# main.net
KiCad netlist of a schematic drawn in Altium Designer
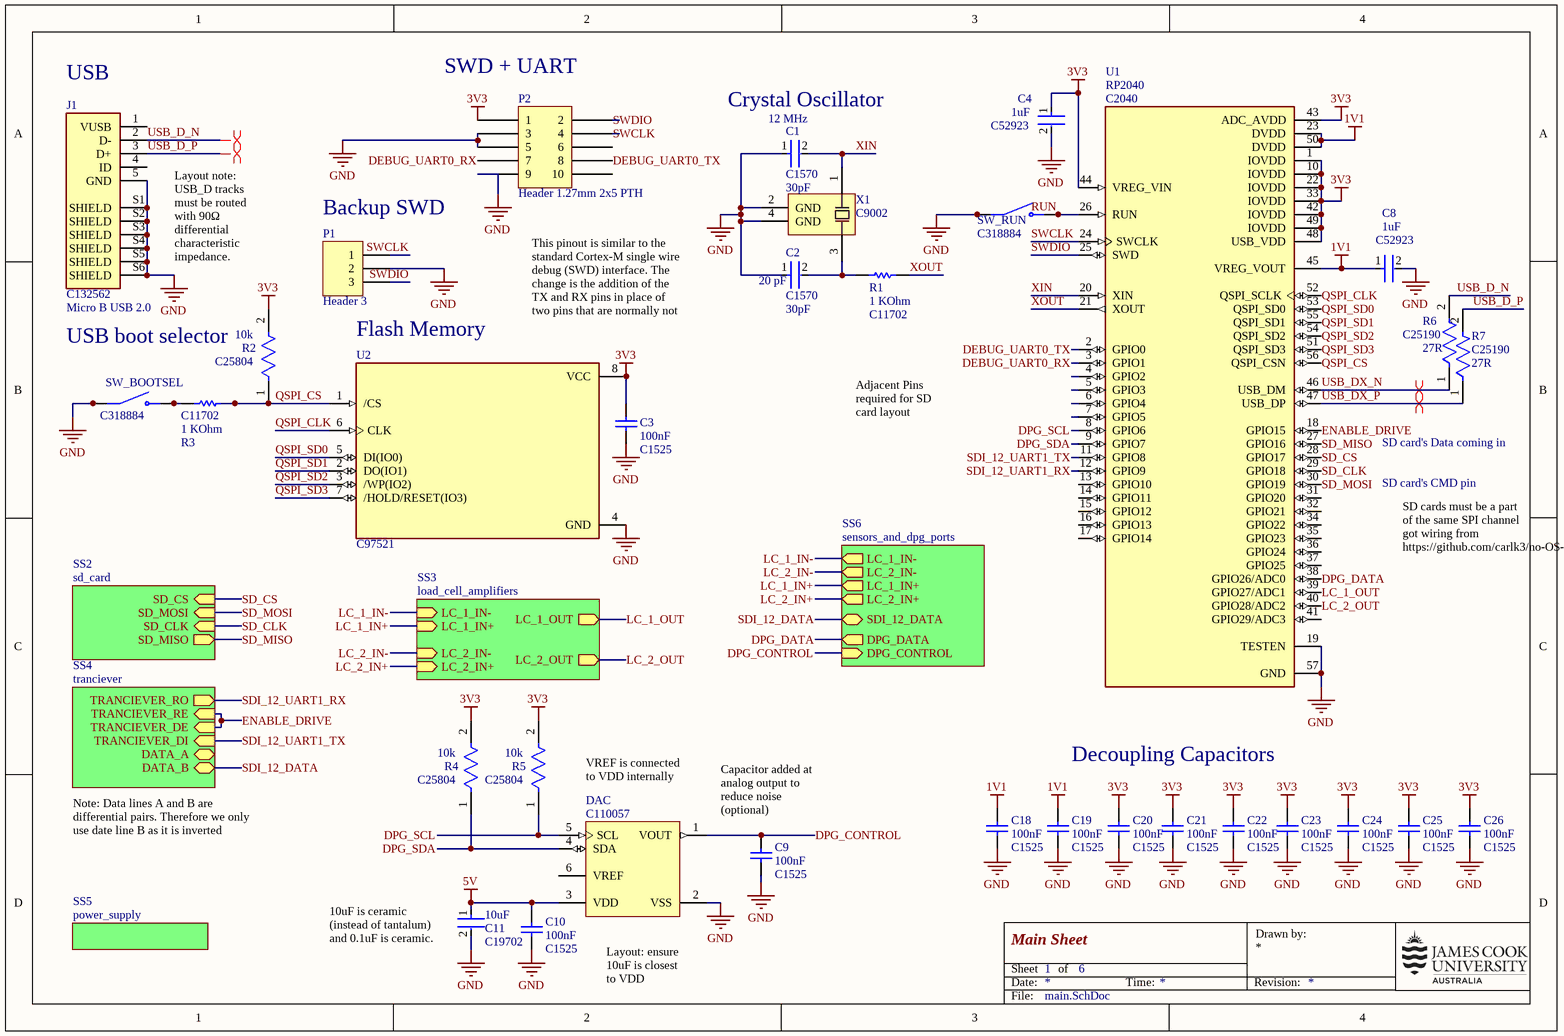
[diagram p0: main.SchDoc]

(export (version "E")
  (design (tool "Eeschema 10.0.6"))
  (components
    (comp (ref "C1")
      (value "0402CG300J500NT")
      (footprint "FP-0402-L_1_0_1-W_0_5_0_1-IPC_B")
      (description "General Purpose Ceramic Capacitor, 0402, 30pF, 5%, C0G, 30ppm/°C, 50V")
      (fields
        (field (name "JLCPCB PART") "C1570")
        (field (name "TOLERANCE") "5%")
        (field (name "VOLTAGE") "50V")
        (field (name "CAPACITANCE") "30pF")
      )
      (libsource (lib "James Cook University") (part "b4654b650e69147ec39a6b967a45e02"))
    )
    (comp (ref "C2")
      (value "0402CG300J500NT")
      (footprint "FP-0402-L_1_0_1-W_0_5_0_1-IPC_B")
      (description "General Purpose Ceramic Capacitor, 0402, 30pF, 5%, C0G, 30ppm/°C, 50V")
      (fields
        (field (name "JLCPCB PART") "C1570")
        (field (name "TOLERANCE") "5%")
        (field (name "VOLTAGE") "50V")
        (field (name "CAPACITANCE") "30pF")
      )
      (libsource (lib "James Cook University") (part "b4654b650e69147ec39a6b967a45e02"))
    )
    (comp (ref "C3")
      (value "CL05B104KO5NNNC")
      (footprint "CAPC1050X55X23NL05T13")
      (description "Chip Capacitor, 100 nF, +/- 10%, 16 V, -55 to 125 degC, 0402 (1005 Metric), RoHS, Tape and Reel")
      (fields
        (field (name "MANUFACTURER") "Samsung Electro-Mechanics")
        (field (name "JLCPCB PART") "C1525")
        (field (name "CAPACITANCE") "100nF")
      )
      (libsource (lib "James Cook University") (part "CAP-NP-2"))
    )
    (comp (ref "C4")
      (value "CL05A105KA5NQNC")
      (footprint "FP-CL542-IPC_B")
      (description "Cap Ceramic 1uF 25V X5R ±10% SMD 0402 +85°C Paper T/R")
      (fields
        (field (name "TOLERANCE") "10%")
        (field (name "CAPACITANCE") "1uF")
        (field (name "JLCPCB PART") "C52923")
      )
      (libsource (lib "James Cook University") (part "b4654b650e69147ec39a6b967a45e02"))
    )
    (comp (ref "C8")
      (value "CL05A105KA5NQNC")
      (footprint "FP-CL542-IPC_B")
      (description "Cap Ceramic 1uF 25V X5R ±10% SMD 0402 +85°C Paper T/R")
      (fields
        (field (name "TOLERANCE") "10%")
        (field (name "CAPACITANCE") "1uF")
        (field (name "JLCPCB PART") "C52923")
      )
      (libsource (lib "James Cook University") (part "b4654b650e69147ec39a6b967a45e02"))
    )
    (comp (ref "C9")
      (value "CL05B104KO5NNNC")
      (footprint "CAPC1050X55X23NL05T13")
      (description "Chip Capacitor, 100 nF, +/- 10%, 16 V, -55 to 125 degC, 0402 (1005 Metric), RoHS, Tape and Reel")
      (fields
        (field (name "MANUFACTURER") "Samsung Electro-Mechanics")
        (field (name "JLCPCB PART") "C1525")
        (field (name "CAPACITANCE") "100nF")
      )
      (libsource (lib "James Cook University") (part "CAP-NP-2"))
    )
    (comp (ref "C10")
      (value "CL05B104KO5NNNC")
      (footprint "CAPC1050X55X23NL05T13")
      (description "Chip Capacitor, 100 nF, +/- 10%, 16 V, -55 to 125 degC, 0402 (1005 Metric), RoHS, Tape and Reel")
      (fields
        (field (name "MANUFACTURER") "Samsung Electro-Mechanics")
        (field (name "JLCPCB PART") "C1525")
        (field (name "CAPACITANCE") "100nF")
      )
      (libsource (lib "James Cook University") (part "CAP-NP-2"))
    )
    (comp (ref "C11")
      (value "CL10A106KP8NNNC")
      (footprint "FP-CL10-IPC_B")
      (description "Cap Ceramic 10uF 10V X5R ±10% Pad SMD 0603 +85°C T/R")
      (fields
        (field (name "JLCPCB PART") "C19702")
        (field (name "CAPACITANCE") "10uF")
        (field (name "TOLERANCE") "10%")
      )
      (libsource (lib "James Cook University") (part "b4654b650e69147ec39a6b967a45e02"))
    )
    (comp (ref "C18")
      (value "CL05B104KO5NNNC")
      (footprint "CAPC1050X55X23NL05T13")
      (description "Chip Capacitor, 100 nF, +/- 10%, 16 V, -55 to 125 degC, 0402 (1005 Metric), RoHS, Tape and Reel")
      (fields
        (field (name "MANUFACTURER") "Samsung Electro-Mechanics")
        (field (name "JLCPCB PART") "C1525")
        (field (name "CAPACITANCE") "100nF")
      )
      (libsource (lib "James Cook University") (part "CAP-NP-2"))
    )
    (comp (ref "C19")
      (value "CL05B104KO5NNNC")
      (footprint "CAPC1050X55X23NL05T13")
      (description "Chip Capacitor, 100 nF, +/- 10%, 16 V, -55 to 125 degC, 0402 (1005 Metric), RoHS, Tape and Reel")
      (fields
        (field (name "MANUFACTURER") "Samsung Electro-Mechanics")
        (field (name "JLCPCB PART") "C1525")
        (field (name "CAPACITANCE") "100nF")
      )
      (libsource (lib "James Cook University") (part "CAP-NP-2"))
    )
    (comp (ref "C20")
      (value "CL05B104KO5NNNC")
      (footprint "CAPC1050X55X23NL05T13")
      (description "Chip Capacitor, 100 nF, +/- 10%, 16 V, -55 to 125 degC, 0402 (1005 Metric), RoHS, Tape and Reel")
      (fields
        (field (name "MANUFACTURER") "Samsung Electro-Mechanics")
        (field (name "JLCPCB PART") "C1525")
        (field (name "CAPACITANCE") "100nF")
      )
      (libsource (lib "James Cook University") (part "CAP-NP-2"))
    )
    (comp (ref "C21")
      (value "CL05B104KO5NNNC")
      (footprint "CAPC1050X55X23NL05T13")
      (description "Chip Capacitor, 100 nF, +/- 10%, 16 V, -55 to 125 degC, 0402 (1005 Metric), RoHS, Tape and Reel")
      (fields
        (field (name "MANUFACTURER") "Samsung Electro-Mechanics")
        (field (name "JLCPCB PART") "C1525")
        (field (name "CAPACITANCE") "100nF")
      )
      (libsource (lib "James Cook University") (part "CAP-NP-2"))
    )
    (comp (ref "C22")
      (value "CL05B104KO5NNNC")
      (footprint "CAPC1050X55X23NL05T13")
      (description "Chip Capacitor, 100 nF, +/- 10%, 16 V, -55 to 125 degC, 0402 (1005 Metric), RoHS, Tape and Reel")
      (fields
        (field (name "MANUFACTURER") "Samsung Electro-Mechanics")
        (field (name "JLCPCB PART") "C1525")
        (field (name "CAPACITANCE") "100nF")
      )
      (libsource (lib "James Cook University") (part "CAP-NP-2"))
    )
    (comp (ref "C23")
      (value "CL05B104KO5NNNC")
      (footprint "CAPC1050X55X23NL05T13")
      (description "Chip Capacitor, 100 nF, +/- 10%, 16 V, -55 to 125 degC, 0402 (1005 Metric), RoHS, Tape and Reel")
      (fields
        (field (name "MANUFACTURER") "Samsung Electro-Mechanics")
        (field (name "JLCPCB PART") "C1525")
        (field (name "CAPACITANCE") "100nF")
      )
      (libsource (lib "James Cook University") (part "CAP-NP-2"))
    )
    (comp (ref "C24")
      (value "CL05B104KO5NNNC")
      (footprint "CAPC1050X55X23NL05T13")
      (description "Chip Capacitor, 100 nF, +/- 10%, 16 V, -55 to 125 degC, 0402 (1005 Metric), RoHS, Tape and Reel")
      (fields
        (field (name "MANUFACTURER") "Samsung Electro-Mechanics")
        (field (name "JLCPCB PART") "C1525")
        (field (name "CAPACITANCE") "100nF")
      )
      (libsource (lib "James Cook University") (part "CAP-NP-2"))
    )
    (comp (ref "C25")
      (value "CL05B104KO5NNNC")
      (footprint "CAPC1050X55X23NL05T13")
      (description "Chip Capacitor, 100 nF, +/- 10%, 16 V, -55 to 125 degC, 0402 (1005 Metric), RoHS, Tape and Reel")
      (fields
        (field (name "MANUFACTURER") "Samsung Electro-Mechanics")
        (field (name "JLCPCB PART") "C1525")
        (field (name "CAPACITANCE") "100nF")
      )
      (libsource (lib "James Cook University") (part "CAP-NP-2"))
    )
    (comp (ref "C26")
      (value "CL05B104KO5NNNC")
      (footprint "CAPC1050X55X23NL05T13")
      (description "Chip Capacitor, 100 nF, +/- 10%, 16 V, -55 to 125 degC, 0402 (1005 Metric), RoHS, Tape and Reel")
      (fields
        (field (name "MANUFACTURER") "Samsung Electro-Mechanics")
        (field (name "JLCPCB PART") "C1525")
        (field (name "CAPACITANCE") "100nF")
      )
      (libsource (lib "James Cook University") (part "CAP-NP-2"))
    )
    (comp (ref "DAC")
      (value "MCP4716A0T-E/CH")
      (footprint "SOT-23-CH6_M")
      (fields (field (name "JLCPCB PART") "C110057"))
      (libsource (lib "Altium Content Vault") (part "CON-DAC-MCP4706-6"))
    )
    (comp (ref "J1")
      (value "Micro B USB 2.0")
      (footprint "FCI_10118193-0001LF")
      (description "USB - micro B USB 2.0 Receptacle Connector 5 Position Surface Mount, Right Angle; Through Hole")
      (fields
        (field (name "MP") "10118193-0001LF")
        (field (name "JLCPCB PART") "C132562")
        (field (name "MF") "Amphenol ICC")
      )
      (libsource (lib "James Cook University") (part "10118193-0001LF"))
    )
    (comp (ref "P1")
      (value "Header 3")
      (footprint "HDR1X3")
      (description "Header, 3-Pin")
      (fields (field (name "PUBLISHER") "Altium Limited"))
      (libsource (lib "James Cook University") (part "Header 3H"))
    )
    (comp (ref "P2")
      (value "Header 1.27mm 2x5 PTH")
      (footprint "Header 1.27mm 2x5 PTH")
      (description "Header 1.27mm pitch, 2x5, PTH through hole")
      (fields (field (name "SOURCE") "JCULibrary.SchLib"))
      (libsource (lib "James Cook University") (part "Header 1.27mm 2x5 PTH"))
    )
    (comp (ref "R1")
      (value "0402WGF1001TCE")
      (footprint "RESC1005X40X25NL05T05")
      (description "Chip Resistor, 1 KOhm, +/- 1%, 100 mW, -55 to 155 degC, 0402 (1005 Metric), RoHS, Tape and Reel")
      (fields
        (field (name "JLCPCB PART") "C11702")
        (field (name "TOLERANCE") "1%")
        (field (name "MANUFACTURER") "Basic Passives")
        (field (name "RESISTANCE") "1 KOhm")
      )
      (libsource (lib "James Cook University") (part "RES-2"))
    )
    (comp (ref "R2")
      (value "0603WAF1002T5E")
      (footprint "FP-CRCW0603-e3-IPC_B")
      (description "RES Thick Film, 10kΩ, 1%, 0.1W, 100ppm/°C, 0603")
      (fields
        (field (name "TOLERANCE") "1%")
        (field (name "JLCPCB PART") "C25804")
        (field (name "RESISTANCE") "10k")
      )
      (libsource (lib "James Cook University") (part "1029c3af85768c4190bb7ad29bc67b5"))
    )
    (comp (ref "R3")
      (value "0402WGF1001TCE")
      (footprint "RESC1005X40X25NL05T05")
      (description "Chip Resistor, 1 KOhm, +/- 1%, 100 mW, -55 to 155 degC, 0402 (1005 Metric), RoHS, Tape and Reel")
      (fields
        (field (name "JLCPCB PART") "C11702")
        (field (name "TOLERANCE") "1%")
        (field (name "MANUFACTURER") "Basic Passives")
        (field (name "RESISTANCE") "1 KOhm")
      )
      (libsource (lib "James Cook University") (part "RES-2"))
    )
    (comp (ref "R4")
      (value "0603WAF1002T5E")
      (footprint "FP-CRCW0603-e3-IPC_B")
      (description "RES Thick Film, 10kΩ, 1%, 0.1W, 100ppm/°C, 0603")
      (fields
        (field (name "TOLERANCE") "1%")
        (field (name "JLCPCB PART") "C25804")
        (field (name "RESISTANCE") "10k")
      )
      (libsource (lib "James Cook University") (part "1029c3af85768c4190bb7ad29bc67b5"))
    )
    (comp (ref "R5")
      (value "0603WAF1002T5E")
      (footprint "FP-CRCW0603-e3-IPC_B")
      (description "RES Thick Film, 10kΩ, 1%, 0.1W, 100ppm/°C, 0603")
      (fields
        (field (name "TOLERANCE") "1%")
        (field (name "JLCPCB PART") "C25804")
        (field (name "RESISTANCE") "10k")
      )
      (libsource (lib "James Cook University") (part "1029c3af85768c4190bb7ad29bc67b5"))
    )
    (comp (ref "R6")
      (value "0603WAF270JT5E")
      (footprint "FP-CRCW0603-e3-IPC_B")
      (description "RES Thick Film, 27Ω, 1%, 0.1W, 200ppm/°C, 0603")
      (fields
        (field (name "TOLERANCE") "1%")
        (field (name "JLCPCB PART") "C25190")
        (field (name "RESISTANCE") "27R")
      )
      (libsource (lib "James Cook University") (part "1029c3af85768c4190bb7ad29bc67b5"))
    )
    (comp (ref "R7")
      (value "0603WAF270JT5E")
      (footprint "FP-CRCW0603-e3-IPC_B")
      (description "RES Thick Film, 27Ω, 1%, 0.1W, 200ppm/°C, 0603")
      (fields
        (field (name "TOLERANCE") "1%")
        (field (name "JLCPCB PART") "C25190")
        (field (name "RESISTANCE") "27R")
      )
      (libsource (lib "James Cook University") (part "1029c3af85768c4190bb7ad29bc67b5"))
    )
    (comp (ref "SW_BOOTSEL")
      (value "TS-1187A-B-A-B")
      (footprint "SW_TS-1187A-B-A-B")
      (description "SPST 50mA @ 12VDC Top Actuated Round Button 160gf SMD Tactile Switches RoHS")
      (fields (field (name "JLCPCB PART") "C318884"))
      (libsource (lib "James Cook University") (part "TS-1187A-B-A-B"))
    )
    (comp (ref "SW_RUN")
      (value "TS-1187A-B-A-B")
      (footprint "SW_TS-1187A-B-A-B")
      (description "SPST 50mA @ 12VDC Top Actuated Round Button 160gf SMD Tactile Switches RoHS")
      (fields (field (name "JLCPCB PART") "C318884"))
      (libsource (lib "James Cook University") (part "TS-1187A-B-A-B"))
    )
    (comp (ref "U1")
      (value "RP2040")
      (footprint "QFN40P700X700X90-57N")
      (description "ARM Cortex-M0+ MCU 32-Bit Microcontroller for Raspberry Pi Pico")
      (fields (field (name "JLCPCB PART") "C2040"))
      (libsource (lib "James Cook University") (part "RP2040"))
    )
    (comp (ref "U2")
      (value "W25Q128JVSIQ")
      (footprint "SOIC127P790X216-8N")
      (description "FLASH - NOR Memory IC 128Mb (16M x 8) SPI - Quad I/O, QPI, DTR 133 MHz 8-SOIC")
      (fields (field (name "JLCPCB PART") "C97521") (field (name "MF") "Winbond Electronics"))
      (libsource (lib "James Cook University") (part "W25Q128JVSIQ"))
    )
    (comp (ref "X1")
      (value "X322512MSB4SI")
      (footprint "X322512MSB4SI-Footprint-1")
      (description "12MHz SMD Crystal Resonator 20pF ±10ppm ±30ppm -40℃~+85℃ SMD3225-4P  Crystals ROHS Yangxing Tech")
      (fields
        (field (name "FREQUENCY") "12 MHz")
        (field (name "JLCPCB PART") "C9002")
        (field (name "LOAD CAPACITANCE") "20 pF")
      )
      (libsource (lib "James Cook University") (part "X322512MSB4SI"))
    )
  )
  (nets
    (net (code "2") (name "/DEBUG_UART0_RX") (class "Default")
      (node (ref "P2") (pin "7") (pinfunction "7_7") (pintype "passive"))
      (node (ref "U1") (pin "3") (pinfunction "GPIO1_3") (pintype "bidirectional"))
    )
    (net (code "3") (name "/DEBUG_UART0_TX") (class "Default")
      (node (ref "P2") (pin "8") (pinfunction "8_8") (pintype "passive"))
      (node (ref "U1") (pin "2") (pinfunction "GPIO0_2") (pintype "bidirectional"))
    )
    (net (code "4") (name "/DPG_CONTROL") (class "Default")
      (node (ref "C9") (pin "2") (pinfunction "2_2") (pintype "passive"))
      (node (ref "DAC") (pin "1") (pinfunction "VOUT_1") (pintype "output"))
    )
    (net (code "5") (name "/DPG_DATA") (class "Default")
      (node (ref "U1") (pin "38") (pinfunction "GPIO26/ADC0_38") (pintype "bidirectional"))
    )
    (net (code "6") (name "/DPG_SCL") (class "Default")
      (node (ref "DAC") (pin "5") (pinfunction "SCL_5") (pintype "input"))
      (node (ref "R5") (pin "1") (pinfunction "1_1") (pintype "passive"))
      (node (ref "U1") (pin "8") (pinfunction "GPIO6_8") (pintype "bidirectional"))
    )
    (net (code "7") (name "/DPG_SDA") (class "Default")
      (node (ref "DAC") (pin "4") (pinfunction "SDA_4") (pintype "bidirectional"))
      (node (ref "R4") (pin "1") (pinfunction "1_1") (pintype "passive"))
      (node (ref "U1") (pin "9") (pinfunction "GPIO7_9") (pintype "bidirectional"))
    )
    (net (code "8") (name "/ENABLE_DRIVE") (class "Default")
      (node (ref "U1") (pin "18") (pinfunction "GPIO15_18") (pintype "bidirectional"))
    )
    (net (code "11") (name "/LC_1_OUT") (class "Default")
      (node (ref "U1") (pin "39") (pinfunction "GPIO27/ADC1_39") (pintype "bidirectional"))
    )
    (net (code "14") (name "/LC_2_OUT") (class "Default")
      (node (ref "U1") (pin "40") (pinfunction "GPIO28/ADC2_40") (pintype "bidirectional"))
    )
    (net (code "15") (name "/QSPI_CLK") (class "Default")
      (node (ref "U1") (pin "52") (pinfunction "QSPI_SCLK_52") (pintype "bidirectional"))
      (node (ref "U2") (pin "6") (pinfunction "CLK_6") (pintype "input"))
    )
    (net (code "16") (name "/QSPI_CS") (class "Default")
      (node (ref "R2") (pin "1") (pinfunction "1_1") (pintype "passive"))
      (node (ref "R3") (pin "2") (pinfunction "2_2") (pintype "passive"))
      (node (ref "U1") (pin "56") (pinfunction "QSPI_CSN_56") (pintype "bidirectional"))
      (node (ref "U2") (pin "1") (pinfunction "/CS_1") (pintype "input"))
    )
    (net (code "17") (name "/QSPI_SD0") (class "Default")
      (node (ref "U1") (pin "53") (pinfunction "QSPI_SD0_53") (pintype "bidirectional"))
      (node (ref "U2") (pin "5") (pinfunction "DI(IO0)_5") (pintype "bidirectional"))
    )
    (net (code "18") (name "/QSPI_SD1") (class "Default")
      (node (ref "U1") (pin "55") (pinfunction "QSPI_SD1_55") (pintype "bidirectional"))
      (node (ref "U2") (pin "2") (pinfunction "DO(IO1)_2") (pintype "bidirectional"))
    )
    (net (code "19") (name "/QSPI_SD2") (class "Default")
      (node (ref "U1") (pin "54") (pinfunction "QSPI_SD2_54") (pintype "bidirectional"))
      (node (ref "U2") (pin "3") (pinfunction "/WP(IO2)_3") (pintype "bidirectional"))
    )
    (net (code "20") (name "/QSPI_SD3") (class "Default")
      (node (ref "U1") (pin "51") (pinfunction "QSPI_SD3_51") (pintype "bidirectional"))
      (node (ref "U2") (pin "7") (pinfunction "/HOLD/RESET(IO3)_7") (pintype "bidirectional"))
    )
    (net (code "21") (name "/RUN") (class "Default")
      (node (ref "SW_RUN") (pin "C") (pinfunction "NO_C") (pintype "passive"))
      (node (ref "SW_RUN") (pin "D") (pinfunction "NO_D") (pintype "passive"))
      (node (ref "U1") (pin "26") (pinfunction "RUN_26") (pintype "input"))
    )
    (net (code "23") (name "/SDI_12_UART1_RX") (class "Default")
      (node (ref "U1") (pin "12") (pinfunction "GPIO9_12") (pintype "bidirectional"))
    )
    (net (code "24") (name "/SDI_12_UART1_TX") (class "Default")
      (node (ref "U1") (pin "11") (pinfunction "GPIO8_11") (pintype "bidirectional"))
    )
    (net (code "25") (name "/SD_CLK") (class "Default")
      (node (ref "U1") (pin "29") (pinfunction "GPIO18_29") (pintype "bidirectional"))
    )
    (net (code "26") (name "/SD_CS") (class "Default")
      (node (ref "U1") (pin "28") (pinfunction "GPIO17_28") (pintype "bidirectional"))
    )
    (net (code "27") (name "/SD_MISO") (class "Default")
      (node (ref "U1") (pin "27") (pinfunction "GPIO16_27") (pintype "bidirectional"))
    )
    (net (code "28") (name "/SD_MOSI") (class "Default")
      (node (ref "U1") (pin "30") (pinfunction "GPIO19_30") (pintype "bidirectional"))
    )
    (net (code "29") (name "/SWCLK") (class "Default")
      (node (ref "P1") (pin "1") (pinfunction "1_1") (pintype "passive"))
      (node (ref "P2") (pin "4") (pinfunction "4_4") (pintype "passive"))
      (node (ref "U1") (pin "24") (pinfunction "SWCLK_24") (pintype "input"))
    )
    (net (code "30") (name "/SWDIO") (class "Default")
      (node (ref "P1") (pin "3") (pinfunction "3_3") (pintype "passive"))
      (node (ref "P2") (pin "2") (pinfunction "2_2") (pintype "passive"))
      (node (ref "U1") (pin "25") (pinfunction "SWD_25") (pintype "bidirectional"))
    )
    (net (code "31") (name "/USB_DX_N") (class "Default")
      (node (ref "R6") (pin "1") (pinfunction "1_1") (pintype "passive"))
      (node (ref "U1") (pin "46") (pinfunction "USB_DM_46") (pintype "bidirectional"))
    )
    (net (code "32") (name "/USB_DX_P") (class "Default")
      (node (ref "R7") (pin "1") (pinfunction "1_1") (pintype "passive"))
      (node (ref "U1") (pin "47") (pinfunction "USB_DP_47") (pintype "bidirectional"))
    )
    (net (code "33") (name "/USB_D_N") (class "Default")
      (node (ref "J1") (pin "2") (pinfunction "D-_2") (pintype "passive"))
      (node (ref "R6") (pin "2") (pinfunction "2_2") (pintype "passive"))
    )
    (net (code "34") (name "/USB_D_P") (class "Default")
      (node (ref "J1") (pin "3") (pinfunction "D+_3") (pintype "passive"))
      (node (ref "R7") (pin "2") (pinfunction "2_2") (pintype "passive"))
    )
    (net (code "35") (name "/XIN") (class "Default")
      (node (ref "C1") (pin "2") (pinfunction "2_2") (pintype "passive"))
      (node (ref "U1") (pin "20") (pinfunction "XIN_20") (pintype "input"))
      (node (ref "X1") (pin "1") (pinfunction "OSC1_1") (pintype "passive"))
    )
    (net (code "36") (name "/XOUT") (class "Default")
      (node (ref "R1") (pin "2") (pinfunction "2_2") (pintype "passive"))
      (node (ref "U1") (pin "21") (pinfunction "XOUT_21") (pintype "output"))
    )
    (net (code "37") (name "1V1") (class "Default")
      (node (ref "C18") (pin "2") (pinfunction "2_2") (pintype "passive"))
      (node (ref "C19") (pin "2") (pinfunction "2_2") (pintype "passive"))
      (node (ref "C8") (pin "1") (pinfunction "1_1") (pintype "passive"))
      (node (ref "U1") (pin "23") (pinfunction "DVDD_23") (pintype "power_in"))
      (node (ref "U1") (pin "45") (pinfunction "VREG_VOUT_45") (pintype "power_in"))
      (node (ref "U1") (pin "50") (pinfunction "DVDD_50") (pintype "power_in"))
    )
    (net (code "38") (name "3V3") (class "Default")
      (node (ref "C20") (pin "2") (pinfunction "2_2") (pintype "passive"))
      (node (ref "C21") (pin "2") (pinfunction "2_2") (pintype "passive"))
      (node (ref "C22") (pin "2") (pinfunction "2_2") (pintype "passive"))
      (node (ref "C23") (pin "2") (pinfunction "2_2") (pintype "passive"))
      (node (ref "C24") (pin "2") (pinfunction "2_2") (pintype "passive"))
      (node (ref "C25") (pin "2") (pinfunction "2_2") (pintype "passive"))
      (node (ref "C26") (pin "2") (pinfunction "2_2") (pintype "passive"))
      (node (ref "C3") (pin "2") (pinfunction "2_2") (pintype "passive"))
      (node (ref "C4") (pin "1") (pinfunction "1_1") (pintype "passive"))
      (node (ref "P2") (pin "1") (pinfunction "1_1") (pintype "passive"))
      (node (ref "R2") (pin "2") (pinfunction "2_2") (pintype "passive"))
      (node (ref "R4") (pin "2") (pinfunction "2_2") (pintype "passive"))
      (node (ref "R5") (pin "2") (pinfunction "2_2") (pintype "passive"))
      (node (ref "U1") (pin "1") (pinfunction "IOVDD_1") (pintype "power_in"))
      (node (ref "U1") (pin "10") (pinfunction "IOVDD_10") (pintype "power_in"))
      (node (ref "U1") (pin "22") (pinfunction "IOVDD_22") (pintype "power_in"))
      (node (ref "U1") (pin "33") (pinfunction "IOVDD_33") (pintype "power_in"))
      (node (ref "U1") (pin "42") (pinfunction "IOVDD_42") (pintype "power_in"))
      (node (ref "U1") (pin "43") (pinfunction "ADC_AVDD_43") (pintype "power_in"))
      (node (ref "U1") (pin "44") (pinfunction "VREG_VIN_44") (pintype "input"))
      (node (ref "U1") (pin "48") (pinfunction "USB_VDD_48") (pintype "power_in"))
      (node (ref "U1") (pin "49") (pinfunction "IOVDD_49") (pintype "power_in"))
      (node (ref "U2") (pin "8") (pinfunction "VCC_8") (pintype "power_in"))
    )
    (net (code "39") (name "5V") (class "Default")
      (node (ref "C10") (pin "2") (pinfunction "2_2") (pintype "passive"))
      (node (ref "C11") (pin "1") (pinfunction "1_1") (pintype "passive"))
      (node (ref "DAC") (pin "3") (pinfunction "VDD_3") (pintype "power_in"))
    )
    (net (code "40") (name "GND") (class "Default")
      (node (ref "C1") (pin "1") (pinfunction "1_1") (pintype "passive"))
      (node (ref "C10") (pin "1") (pinfunction "1_1") (pintype "passive"))
      (node (ref "C11") (pin "2") (pinfunction "2_2") (pintype "passive"))
      (node (ref "C18") (pin "1") (pinfunction "1_1") (pintype "passive"))
      (node (ref "C19") (pin "1") (pinfunction "1_1") (pintype "passive"))
      (node (ref "C2") (pin "1") (pinfunction "1_1") (pintype "passive"))
      (node (ref "C20") (pin "1") (pinfunction "1_1") (pintype "passive"))
      (node (ref "C21") (pin "1") (pinfunction "1_1") (pintype "passive"))
      (node (ref "C22") (pin "1") (pinfunction "1_1") (pintype "passive"))
      (node (ref "C23") (pin "1") (pinfunction "1_1") (pintype "passive"))
      (node (ref "C24") (pin "1") (pinfunction "1_1") (pintype "passive"))
      (node (ref "C25") (pin "1") (pinfunction "1_1") (pintype "passive"))
      (node (ref "C26") (pin "1") (pinfunction "1_1") (pintype "passive"))
      (node (ref "C3") (pin "1") (pinfunction "1_1") (pintype "passive"))
      (node (ref "C4") (pin "2") (pinfunction "2_2") (pintype "passive"))
      (node (ref "C8") (pin "2") (pinfunction "2_2") (pintype "passive"))
      (node (ref "C9") (pin "1") (pinfunction "1_1") (pintype "passive"))
      (node (ref "DAC") (pin "2") (pinfunction "VSS_2") (pintype "power_in"))
      (node (ref "J1") (pin "5") (pinfunction "GND_5") (pintype "passive"))
      (node (ref "J1") (pin "S1") (pinfunction "SHIELD_S1") (pintype "passive"))
      (node (ref "J1") (pin "S2") (pinfunction "SHIELD_S2") (pintype "passive"))
      (node (ref "J1") (pin "S3") (pinfunction "SHIELD_S3") (pintype "passive"))
      (node (ref "J1") (pin "S4") (pinfunction "SHIELD_S4") (pintype "passive"))
      (node (ref "J1") (pin "S5") (pinfunction "SHIELD_S5") (pintype "passive"))
      (node (ref "J1") (pin "S6") (pinfunction "SHIELD_S6") (pintype "passive"))
      (node (ref "P1") (pin "2") (pinfunction "2_2") (pintype "passive"))
      (node (ref "P2") (pin "3") (pinfunction "3_3") (pintype "passive"))
      (node (ref "P2") (pin "5") (pinfunction "5_5") (pintype "passive"))
      (node (ref "P2") (pin "9") (pinfunction "9_9") (pintype "passive"))
      (node (ref "SW_BOOTSEL") (pin "A") (pinfunction "COM_A") (pintype "passive"))
      (node (ref "SW_BOOTSEL") (pin "B") (pinfunction "COM_B") (pintype "passive"))
      (node (ref "SW_RUN") (pin "A") (pinfunction "COM_A") (pintype "passive"))
      (node (ref "SW_RUN") (pin "B") (pinfunction "COM_B") (pintype "passive"))
      (node (ref "U1") (pin "19") (pinfunction "TESTEN_19") (pintype "passive"))
      (node (ref "U1") (pin "57") (pinfunction "GND_57") (pintype "power_in"))
      (node (ref "U2") (pin "4") (pinfunction "GND_4") (pintype "power_in"))
      (node (ref "X1") (pin "2") (pinfunction "GND_2") (pintype "passive"))
      (node (ref "X1") (pin "4") (pinfunction "GND_4") (pintype "passive"))
    )
    (net (code "41") (name "Net-(R3-Pad1)") (class "Default")
      (node (ref "R3") (pin "1") (pinfunction "1_1") (pintype "passive"))
      (node (ref "SW_BOOTSEL") (pin "C") (pinfunction "NO_C") (pintype "passive"))
      (node (ref "SW_BOOTSEL") (pin "D") (pinfunction "NO_D") (pintype "passive"))
    )
    (net (code "42") (name "Net-(X1-OSC2)") (class "Default")
      (node (ref "C2") (pin "2") (pinfunction "2_2") (pintype "passive"))
      (node (ref "R1") (pin "1") (pinfunction "1_1") (pintype "passive"))
      (node (ref "X1") (pin "3") (pinfunction "OSC2_3") (pintype "passive"))
    )
    (net (code "43") (name "unconnected-(DAC-VREF-Pad6)") (class "Default")
      (node (ref "DAC") (pin "6") (pinfunction "VREF_6") (pintype "power_in"))
    )
    (net (code "44") (name "unconnected-(J1-ID-Pad4)") (class "Default")
      (node (ref "J1") (pin "4") (pinfunction "ID_4") (pintype "passive"))
    )
    (net (code "45") (name "unconnected-(J1-VUSB-Pad1)") (class "Default")
      (node (ref "J1") (pin "1") (pinfunction "VUSB_1") (pintype "passive"))
    )
    (net (code "46") (name "unconnected-(P2-Pad6)") (class "Default")
      (node (ref "P2") (pin "6") (pinfunction "6_6") (pintype "passive"))
    )
    (net (code "47") (name "unconnected-(P2-Pad10)") (class "Default")
      (node (ref "P2") (pin "10") (pinfunction "10_10") (pintype "passive"))
    )
    (net (code "48") (name "unconnected-(U1-GPIO2-Pad4)") (class "Default")
      (node (ref "U1") (pin "4") (pinfunction "GPIO2_4") (pintype "bidirectional"))
    )
    (net (code "49") (name "unconnected-(U1-GPIO3-Pad5)") (class "Default")
      (node (ref "U1") (pin "5") (pinfunction "GPIO3_5") (pintype "bidirectional"))
    )
    (net (code "50") (name "unconnected-(U1-GPIO4-Pad6)") (class "Default")
      (node (ref "U1") (pin "6") (pinfunction "GPIO4_6") (pintype "bidirectional"))
    )
    (net (code "51") (name "unconnected-(U1-GPIO5-Pad7)") (class "Default")
      (node (ref "U1") (pin "7") (pinfunction "GPIO5_7") (pintype "bidirectional"))
    )
    (net (code "52") (name "unconnected-(U1-GPIO10-Pad13)") (class "Default")
      (node (ref "U1") (pin "13") (pinfunction "GPIO10_13") (pintype "bidirectional"))
    )
    (net (code "53") (name "unconnected-(U1-GPIO11-Pad14)") (class "Default")
      (node (ref "U1") (pin "14") (pinfunction "GPIO11_14") (pintype "bidirectional"))
    )
    (net (code "54") (name "unconnected-(U1-GPIO12-Pad15)") (class "Default")
      (node (ref "U1") (pin "15") (pinfunction "GPIO12_15") (pintype "bidirectional"))
    )
    (net (code "55") (name "unconnected-(U1-GPIO13-Pad16)") (class "Default")
      (node (ref "U1") (pin "16") (pinfunction "GPIO13_16") (pintype "bidirectional"))
    )
    (net (code "56") (name "unconnected-(U1-GPIO14-Pad17)") (class "Default")
      (node (ref "U1") (pin "17") (pinfunction "GPIO14_17") (pintype "bidirectional"))
    )
    (net (code "57") (name "unconnected-(U1-GPIO20-Pad31)") (class "Default")
      (node (ref "U1") (pin "31") (pinfunction "GPIO20_31") (pintype "bidirectional"))
    )
    (net (code "58") (name "unconnected-(U1-GPIO21-Pad32)") (class "Default")
      (node (ref "U1") (pin "32") (pinfunction "GPIO21_32") (pintype "bidirectional"))
    )
    (net (code "59") (name "unconnected-(U1-GPIO22-Pad34)") (class "Default")
      (node (ref "U1") (pin "34") (pinfunction "GPIO22_34") (pintype "bidirectional"))
    )
    (net (code "60") (name "unconnected-(U1-GPIO23-Pad35)") (class "Default")
      (node (ref "U1") (pin "35") (pinfunction "GPIO23_35") (pintype "bidirectional"))
    )
    (net (code "61") (name "unconnected-(U1-GPIO24-Pad36)") (class "Default")
      (node (ref "U1") (pin "36") (pinfunction "GPIO24_36") (pintype "bidirectional"))
    )
    (net (code "62") (name "unconnected-(U1-GPIO25-Pad37)") (class "Default")
      (node (ref "U1") (pin "37") (pinfunction "GPIO25_37") (pintype "bidirectional"))
    )
    (net (code "63") (name "unconnected-(U1-GPIO29{slash}ADC3-Pad41)") (class "Default")
      (node (ref "U1") (pin "41") (pinfunction "GPIO29/ADC3_41") (pintype "bidirectional"))
    )
  )
)
